# Interface_board.net
KiCad netlist of a schematic drawn in EAGLE
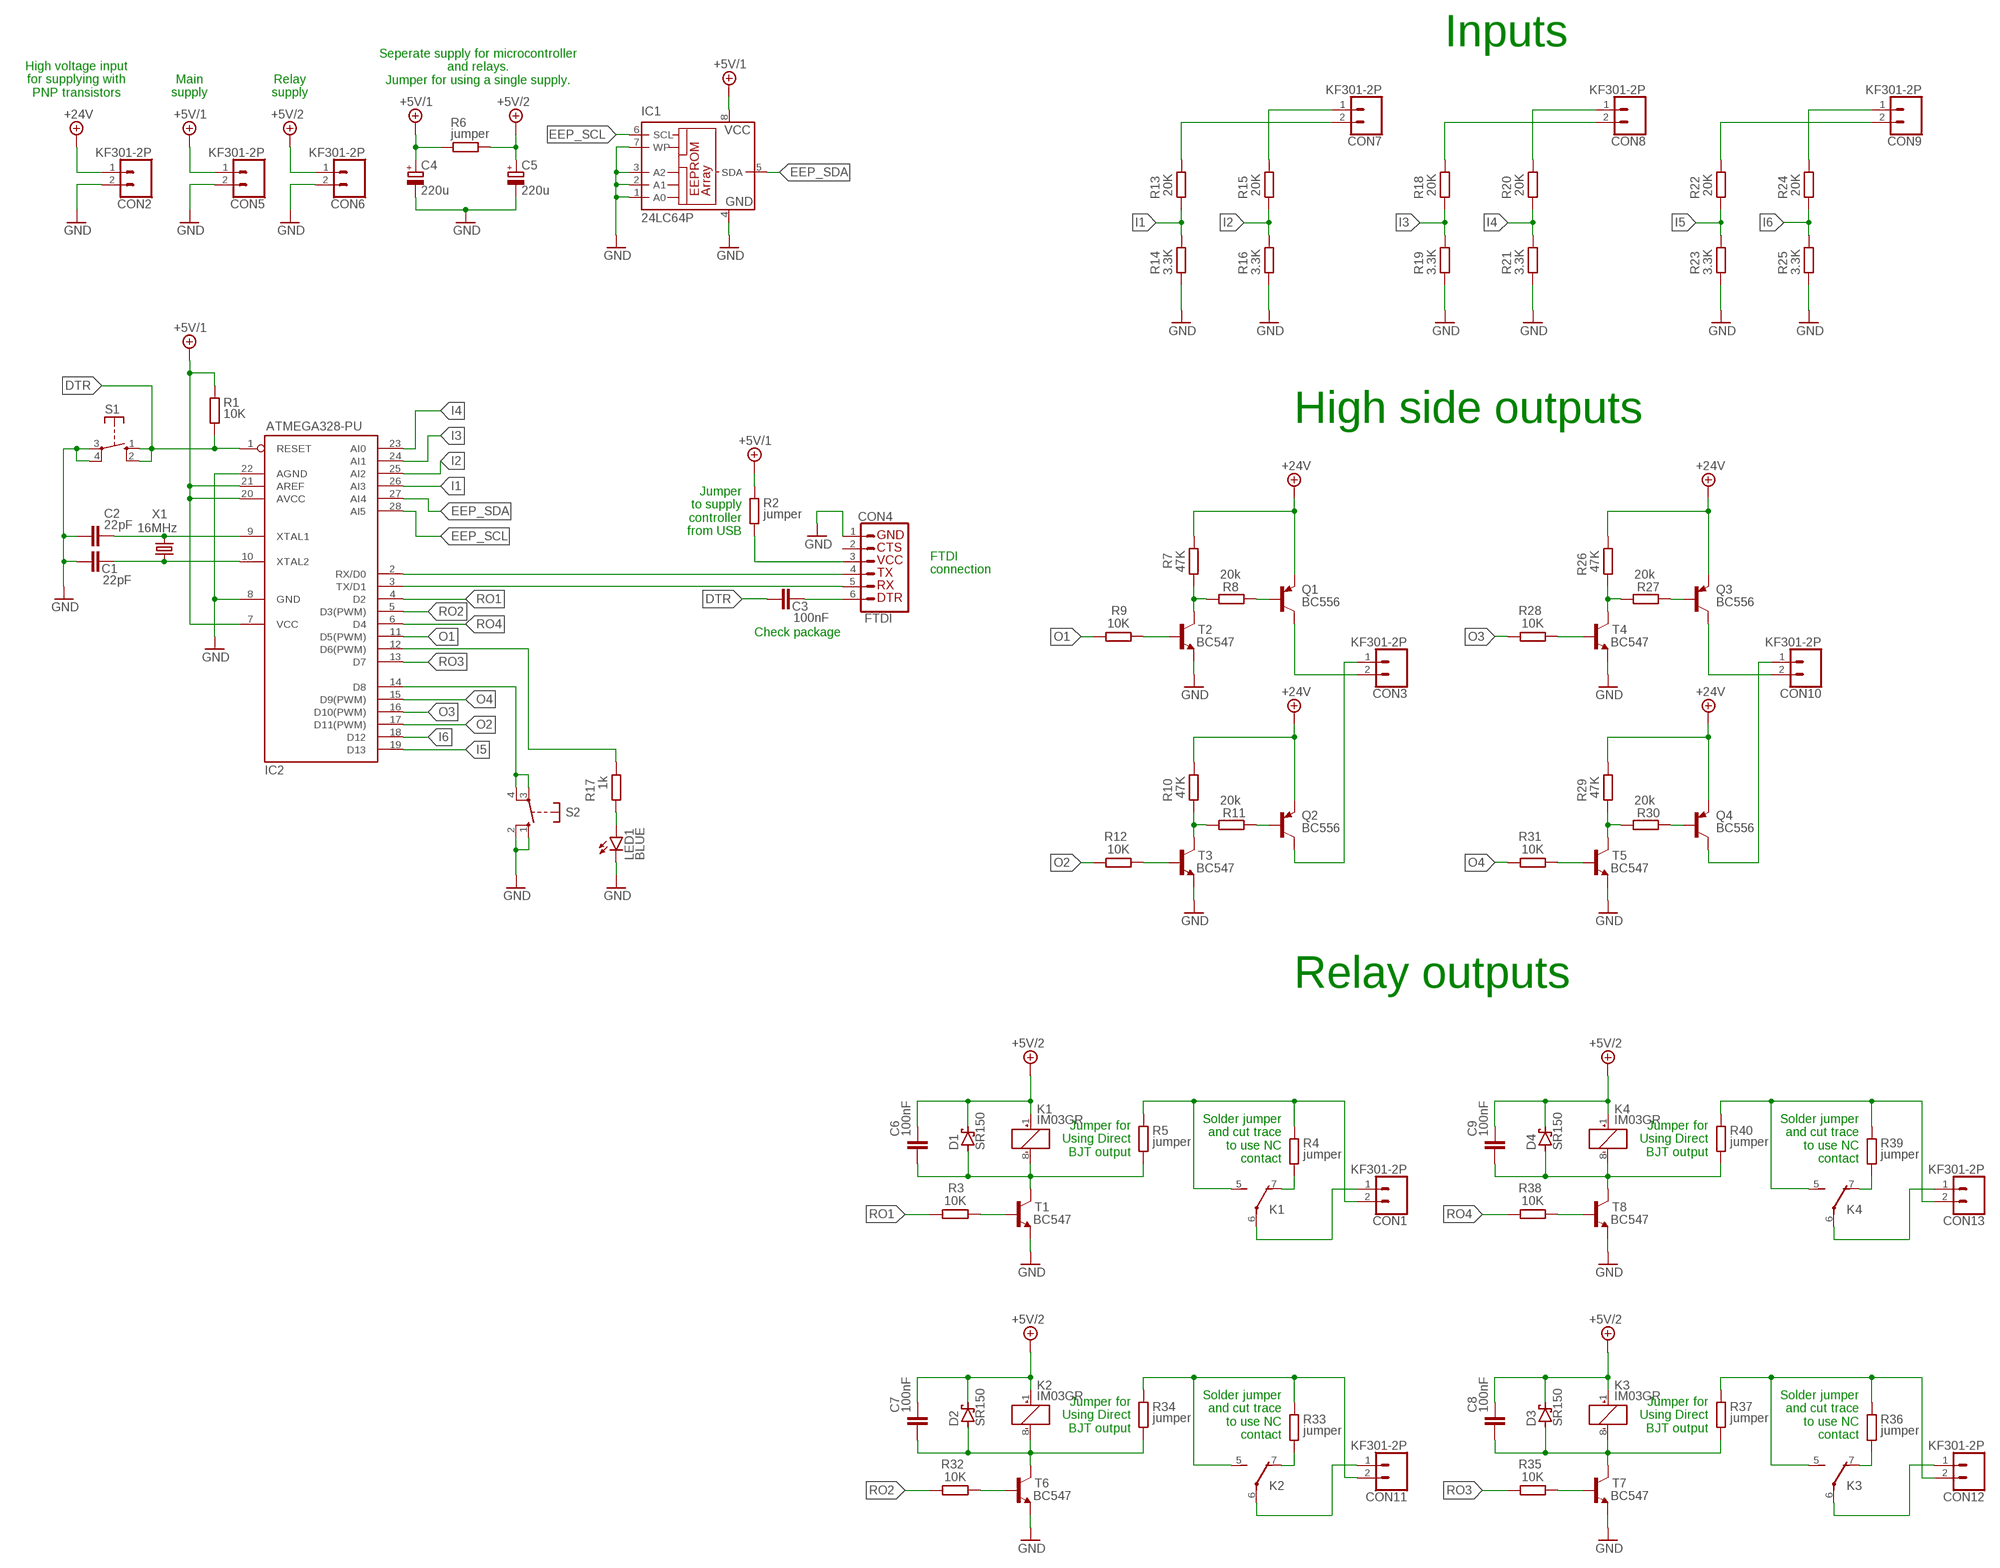
[diagram p0: schematic, sheet 1]

(export (version "E")
  (design (tool "Eeschema 10.0.6"))
  (components
    (comp (ref "C1")
      (value "22pF")
      (footprint "eagle-import:C050-024X044")
      (libsource (lib "eagle-import") (part "C-EU050-024X044"))
    )
    (comp (ref "C2")
      (value "22pF")
      (footprint "eagle-import:C050-024X044")
      (libsource (lib "eagle-import") (part "C-EU050-024X044"))
    )
    (comp (ref "C3")
      (value "100nF")
      (footprint "eagle-import:C050-024X044")
      (libsource (lib "eagle-import") (part "C-EU050-024X044"))
    )
    (comp (ref "C4")
      (value "220u")
      (footprint "eagle-import:E5-10,5")
      (libsource (lib "eagle-import") (part "CPOL-EUE5-10.5"))
    )
    (comp (ref "C5")
      (value "220u")
      (footprint "eagle-import:E5-10,5")
      (libsource (lib "eagle-import") (part "CPOL-EUE5-10.5"))
    )
    (comp (ref "C6")
      (value "100nF")
      (footprint "eagle-import:C050-024X044")
      (libsource (lib "eagle-import") (part "C-EU050-024X044"))
    )
    (comp (ref "C7")
      (value "100nF")
      (footprint "eagle-import:C050-024X044")
      (libsource (lib "eagle-import") (part "C-EU050-024X044"))
    )
    (comp (ref "C8")
      (value "100nF")
      (footprint "eagle-import:C050-024X044")
      (libsource (lib "eagle-import") (part "C-EU050-024X044"))
    )
    (comp (ref "C9")
      (value "100nF")
      (footprint "eagle-import:C050-024X044")
      (libsource (lib "eagle-import") (part "C-EU050-024X044"))
    )
    (comp (ref "CON1")
      (value "KF301-2P")
      (footprint "eagle-import:KF301-2P")
      (libsource (lib "eagle-import") (part "KF301-2P"))
    )
    (comp (ref "CON2")
      (value "KF301-2P")
      (footprint "eagle-import:KF301-2P")
      (libsource (lib "eagle-import") (part "KF301-2P"))
    )
    (comp (ref "CON3")
      (value "KF301-2P")
      (footprint "eagle-import:KF301-2P")
      (libsource (lib "eagle-import") (part "KF301-2P"))
    )
    (comp (ref "CON4")
      (value "FTDI")
      (footprint "eagle-import:1X06_W_REC_GND")
      (libsource (lib "eagle-import") (part "FTDI_CONN"))
    )
    (comp (ref "CON5")
      (value "KF301-2P")
      (footprint "eagle-import:KF301-2P")
      (libsource (lib "eagle-import") (part "KF301-2P"))
    )
    (comp (ref "CON6")
      (value "KF301-2P")
      (footprint "eagle-import:KF301-2P")
      (libsource (lib "eagle-import") (part "KF301-2P"))
    )
    (comp (ref "CON7")
      (value "KF301-2P")
      (footprint "eagle-import:KF301-2P")
      (libsource (lib "eagle-import") (part "KF301-2P"))
    )
    (comp (ref "CON8")
      (value "KF301-2P")
      (footprint "eagle-import:KF301-2P")
      (libsource (lib "eagle-import") (part "KF301-2P"))
    )
    (comp (ref "CON9")
      (value "KF301-2P")
      (footprint "eagle-import:KF301-2P")
      (libsource (lib "eagle-import") (part "KF301-2P"))
    )
    (comp (ref "CON10")
      (value "KF301-2P")
      (footprint "eagle-import:KF301-2P")
      (libsource (lib "eagle-import") (part "KF301-2P"))
    )
    (comp (ref "CON11")
      (value "KF301-2P")
      (footprint "eagle-import:KF301-2P")
      (libsource (lib "eagle-import") (part "KF301-2P"))
    )
    (comp (ref "CON12")
      (value "KF301-2P")
      (footprint "eagle-import:KF301-2P")
      (libsource (lib "eagle-import") (part "KF301-2P"))
    )
    (comp (ref "CON13")
      (value "KF301-2P")
      (footprint "eagle-import:KF301-2P")
      (libsource (lib "eagle-import") (part "KF301-2P"))
    )
    (comp (ref "D1")
      (value "SR150")
      (footprint "eagle-import:DO41-7.6")
      (libsource (lib "eagle-import") (part "1N5817-B"))
    )
    (comp (ref "D2")
      (value "SR150")
      (footprint "eagle-import:DO41-7.6")
      (libsource (lib "eagle-import") (part "1N5817-B"))
    )
    (comp (ref "D3")
      (value "SR150")
      (footprint "eagle-import:DO41-7.6")
      (libsource (lib "eagle-import") (part "1N5817-B"))
    )
    (comp (ref "D4")
      (value "SR150")
      (footprint "eagle-import:DO41-7.6")
      (libsource (lib "eagle-import") (part "1N5817-B"))
    )
    (comp (ref "IC1")
      (value "24LC64P")
      (footprint "eagle-import:DIL8")
      (fields (field (name "MF") "MICROCHIP") (field (name "MPN") "24LC64-I/P"))
      (libsource (lib "eagle-import") (part "24PLC64"))
    )
    (comp (ref "IC2")
      (value "ATMEGA328-PU")
      (footprint "eagle-import:DIL28-3")
      (libsource (lib "eagle-import") (part "328-PU_ARDUINO_F"))
    )
    (comp (ref "K1")
      (value "IM03GR")
      (footprint "eagle-import:IM03GR")
      (libsource (lib "eagle-import") (part "IM03GR"))
    )
    (comp (ref "K2")
      (value "IM03GR")
      (footprint "eagle-import:IM03GR")
      (libsource (lib "eagle-import") (part "IM03GR"))
    )
    (comp (ref "K3")
      (value "IM03GR")
      (footprint "eagle-import:IM03GR")
      (libsource (lib "eagle-import") (part "IM03GR"))
    )
    (comp (ref "K4")
      (value "IM03GR")
      (footprint "eagle-import:IM03GR")
      (libsource (lib "eagle-import") (part "IM03GR"))
    )
    (comp (ref "LED1")
      (value "BLUE")
      (footprint "eagle-import:LED5MM")
      (libsource (lib "eagle-import") (part "LED5MM"))
    )
    (comp (ref "Q1")
      (value "BC556")
      (footprint "eagle-import:TO92-EBC")
      (libsource (lib "eagle-import") (part "BC556"))
    )
    (comp (ref "Q2")
      (value "BC556")
      (footprint "eagle-import:TO92-EBC")
      (libsource (lib "eagle-import") (part "BC556"))
    )
    (comp (ref "Q3")
      (value "BC556")
      (footprint "eagle-import:TO92-EBC")
      (libsource (lib "eagle-import") (part "BC556"))
    )
    (comp (ref "Q4")
      (value "BC556")
      (footprint "eagle-import:TO92-EBC")
      (libsource (lib "eagle-import") (part "BC556"))
    )
    (comp (ref "R1")
      (value "10K")
      (footprint "eagle-import:0204_7")
      (libsource (lib "eagle-import") (part "R-EU_0204/7"))
    )
    (comp (ref "R2")
      (value "jumper")
      (footprint "eagle-import:R0805")
      (libsource (lib "eagle-import") (part "R-EU_R0805"))
    )
    (comp (ref "R3")
      (value "10K")
      (footprint "eagle-import:0204_7")
      (libsource (lib "eagle-import") (part "R-EU_0204/7"))
    )
    (comp (ref "R4")
      (value "jumper")
      (footprint "eagle-import:R0805")
      (libsource (lib "eagle-import") (part "R-EU_R0805"))
    )
    (comp (ref "R5")
      (value "jumper")
      (footprint "eagle-import:R0805")
      (libsource (lib "eagle-import") (part "R-EU_R0805"))
    )
    (comp (ref "R6")
      (value "jumper")
      (footprint "eagle-import:R0805")
      (libsource (lib "eagle-import") (part "R-EU_R0805"))
    )
    (comp (ref "R7")
      (value "47K")
      (footprint "eagle-import:0204_7")
      (libsource (lib "eagle-import") (part "R-EU_0204/7"))
    )
    (comp (ref "R8")
      (value "20k")
      (footprint "eagle-import:0204_7")
      (libsource (lib "eagle-import") (part "R-EU_0204/7"))
    )
    (comp (ref "R9")
      (value "10K")
      (footprint "eagle-import:0204_7")
      (libsource (lib "eagle-import") (part "R-EU_0204/7"))
    )
    (comp (ref "R10")
      (value "47K")
      (footprint "eagle-import:0204_7")
      (libsource (lib "eagle-import") (part "R-EU_0204/7"))
    )
    (comp (ref "R11")
      (value "20k")
      (footprint "eagle-import:0204_7")
      (libsource (lib "eagle-import") (part "R-EU_0204/7"))
    )
    (comp (ref "R12")
      (value "10K")
      (footprint "eagle-import:0204_7")
      (libsource (lib "eagle-import") (part "R-EU_0204/7"))
    )
    (comp (ref "R13")
      (value "20K")
      (footprint "eagle-import:0204_7")
      (libsource (lib "eagle-import") (part "R-EU_0204/7"))
    )
    (comp (ref "R14")
      (value "3.3K")
      (footprint "eagle-import:0204_7")
      (libsource (lib "eagle-import") (part "R-EU_0204/7"))
    )
    (comp (ref "R15")
      (value "20K")
      (footprint "eagle-import:0204_7")
      (libsource (lib "eagle-import") (part "R-EU_0204/7"))
    )
    (comp (ref "R16")
      (value "3.3K")
      (footprint "eagle-import:0204_7")
      (libsource (lib "eagle-import") (part "R-EU_0204/7"))
    )
    (comp (ref "R17")
      (value "1k")
      (footprint "eagle-import:0204_7")
      (libsource (lib "eagle-import") (part "R-EU_0204/7"))
    )
    (comp (ref "R18")
      (value "20K")
      (footprint "eagle-import:0204_7")
      (libsource (lib "eagle-import") (part "R-EU_0204/7"))
    )
    (comp (ref "R19")
      (value "3.3K")
      (footprint "eagle-import:0204_7")
      (libsource (lib "eagle-import") (part "R-EU_0204/7"))
    )
    (comp (ref "R20")
      (value "20K")
      (footprint "eagle-import:0204_7")
      (libsource (lib "eagle-import") (part "R-EU_0204/7"))
    )
    (comp (ref "R21")
      (value "3.3K")
      (footprint "eagle-import:0204_7")
      (libsource (lib "eagle-import") (part "R-EU_0204/7"))
    )
    (comp (ref "R22")
      (value "20K")
      (footprint "eagle-import:0204_7")
      (libsource (lib "eagle-import") (part "R-EU_0204/7"))
    )
    (comp (ref "R23")
      (value "3.3K")
      (footprint "eagle-import:0204_7")
      (libsource (lib "eagle-import") (part "R-EU_0204/7"))
    )
    (comp (ref "R24")
      (value "20K")
      (footprint "eagle-import:0204_7")
      (libsource (lib "eagle-import") (part "R-EU_0204/7"))
    )
    (comp (ref "R25")
      (value "3.3K")
      (footprint "eagle-import:0204_7")
      (libsource (lib "eagle-import") (part "R-EU_0204/7"))
    )
    (comp (ref "R26")
      (value "47K")
      (footprint "eagle-import:0204_7")
      (libsource (lib "eagle-import") (part "R-EU_0204/7"))
    )
    (comp (ref "R27")
      (value "20k")
      (footprint "eagle-import:0204_7")
      (libsource (lib "eagle-import") (part "R-EU_0204/7"))
    )
    (comp (ref "R28")
      (value "10K")
      (footprint "eagle-import:0204_7")
      (libsource (lib "eagle-import") (part "R-EU_0204/7"))
    )
    (comp (ref "R29")
      (value "47K")
      (footprint "eagle-import:0204_7")
      (libsource (lib "eagle-import") (part "R-EU_0204/7"))
    )
    (comp (ref "R30")
      (value "20k")
      (footprint "eagle-import:0204_7")
      (libsource (lib "eagle-import") (part "R-EU_0204/7"))
    )
    (comp (ref "R31")
      (value "10K")
      (footprint "eagle-import:0204_7")
      (libsource (lib "eagle-import") (part "R-EU_0204/7"))
    )
    (comp (ref "R32")
      (value "10K")
      (footprint "eagle-import:0204_7")
      (libsource (lib "eagle-import") (part "R-EU_0204/7"))
    )
    (comp (ref "R33")
      (value "jumper")
      (footprint "eagle-import:R0805")
      (libsource (lib "eagle-import") (part "R-EU_R0805"))
    )
    (comp (ref "R34")
      (value "jumper")
      (footprint "eagle-import:R0805")
      (libsource (lib "eagle-import") (part "R-EU_R0805"))
    )
    (comp (ref "R35")
      (value "10K")
      (footprint "eagle-import:0204_7")
      (libsource (lib "eagle-import") (part "R-EU_0204/7"))
    )
    (comp (ref "R36")
      (value "jumper")
      (footprint "eagle-import:R0805")
      (libsource (lib "eagle-import") (part "R-EU_R0805"))
    )
    (comp (ref "R37")
      (value "jumper")
      (footprint "eagle-import:R0805")
      (libsource (lib "eagle-import") (part "R-EU_R0805"))
    )
    (comp (ref "R38")
      (value "10K")
      (footprint "eagle-import:0204_7")
      (libsource (lib "eagle-import") (part "R-EU_0204/7"))
    )
    (comp (ref "R39")
      (value "jumper")
      (footprint "eagle-import:R0805")
      (libsource (lib "eagle-import") (part "R-EU_R0805"))
    )
    (comp (ref "R40")
      (value "jumper")
      (footprint "eagle-import:R0805")
      (libsource (lib "eagle-import") (part "R-EU_R0805"))
    )
    (comp (ref "S1")
      (value "RACON12")
      (footprint "eagle-import:RACON12")
      (libsource (lib "eagle-import") (part "RACON12"))
    )
    (comp (ref "S2")
      (value "RACON12")
      (footprint "eagle-import:RACON12")
      (libsource (lib "eagle-import") (part "RACON12"))
    )
    (comp (ref "T1")
      (value "BC547")
      (footprint "eagle-import:TO92")
      (libsource (lib "eagle-import") (part "BC547"))
    )
    (comp (ref "T2")
      (value "BC547")
      (footprint "eagle-import:TO92")
      (libsource (lib "eagle-import") (part "BC547"))
    )
    (comp (ref "T3")
      (value "BC547")
      (footprint "eagle-import:TO92")
      (libsource (lib "eagle-import") (part "BC547"))
    )
    (comp (ref "T4")
      (value "BC547")
      (footprint "eagle-import:TO92")
      (libsource (lib "eagle-import") (part "BC547"))
    )
    (comp (ref "T5")
      (value "BC547")
      (footprint "eagle-import:TO92")
      (libsource (lib "eagle-import") (part "BC547"))
    )
    (comp (ref "T6")
      (value "BC547")
      (footprint "eagle-import:TO92")
      (libsource (lib "eagle-import") (part "BC547"))
    )
    (comp (ref "T7")
      (value "BC547")
      (footprint "eagle-import:TO92")
      (libsource (lib "eagle-import") (part "BC547"))
    )
    (comp (ref "T8")
      (value "BC547")
      (footprint "eagle-import:TO92")
      (libsource (lib "eagle-import") (part "BC547"))
    )
    (comp (ref "X1")
      (value "16MHz")
      (footprint "eagle-import:HC49")
      (libsource (lib "eagle-import") (part "CRYSTALS-NOGND-HC49"))
    )
  )
  (nets
    (net (code "1") (name "+5V{slash}1") (class "Default")
      (node (ref "C4") (pin "+") (pinfunction "+_+") (pintype "passive"))
      (node (ref "CON5") (pin "1") (pinfunction "1_1") (pintype "passive"))
      (node (ref "IC1") (pin "8") (pinfunction "VCC_8") (pintype "power_in"))
      (node (ref "IC2") (pin "20") (pinfunction "AVCC_20") (pintype "bidirectional"))
      (node (ref "IC2") (pin "21") (pinfunction "AREF_21") (pintype "bidirectional"))
      (node (ref "IC2") (pin "7") (pinfunction "VCC_7") (pintype "bidirectional"))
      (node (ref "R1") (pin "1") (pinfunction "1_1") (pintype "passive"))
      (node (ref "R2") (pin "1") (pinfunction "1_1") (pintype "passive"))
      (node (ref "R6") (pin "1") (pinfunction "1_1") (pintype "passive"))
    )
    (net (code "2") (name "+5V{slash}2") (class "Default")
      (node (ref "C5") (pin "+") (pinfunction "+_+") (pintype "passive"))
      (node (ref "C6") (pin "1") (pinfunction "1_1") (pintype "passive"))
      (node (ref "C7") (pin "1") (pinfunction "1_1") (pintype "passive"))
      (node (ref "C8") (pin "1") (pinfunction "1_1") (pintype "passive"))
      (node (ref "C9") (pin "1") (pinfunction "1_1") (pintype "passive"))
      (node (ref "CON6") (pin "1") (pinfunction "1_1") (pintype "passive"))
      (node (ref "D1") (pin "C") (pinfunction "C_C") (pintype "passive"))
      (node (ref "D2") (pin "C") (pinfunction "C_C") (pintype "passive"))
      (node (ref "D3") (pin "C") (pinfunction "C_C") (pintype "passive"))
      (node (ref "D4") (pin "C") (pinfunction "C_C") (pintype "passive"))
      (node (ref "K1") (pin "1") (pinfunction "+_1") (pintype "passive"))
      (node (ref "K2") (pin "1") (pinfunction "+_1") (pintype "passive"))
      (node (ref "K3") (pin "1") (pinfunction "+_1") (pintype "passive"))
      (node (ref "K4") (pin "1") (pinfunction "+_1") (pintype "passive"))
      (node (ref "R6") (pin "2") (pinfunction "2_2") (pintype "passive"))
    )
    (net (code "3") (name "+24V") (class "Default")
      (node (ref "CON2") (pin "1") (pinfunction "1_1") (pintype "passive"))
      (node (ref "Q1") (pin "E") (pinfunction "E_E") (pintype "passive"))
      (node (ref "Q2") (pin "E") (pinfunction "E_E") (pintype "passive"))
      (node (ref "Q3") (pin "E") (pinfunction "E_E") (pintype "passive"))
      (node (ref "Q4") (pin "E") (pinfunction "E_E") (pintype "passive"))
      (node (ref "R10") (pin "2") (pinfunction "2_2") (pintype "passive"))
      (node (ref "R26") (pin "2") (pinfunction "2_2") (pintype "passive"))
      (node (ref "R29") (pin "2") (pinfunction "2_2") (pintype "passive"))
      (node (ref "R7") (pin "2") (pinfunction "2_2") (pintype "passive"))
    )
    (net (code "4") (name "DTR") (class "Default")
      (node (ref "C3") (pin "2") (pinfunction "2_2") (pintype "passive"))
      (node (ref "IC2") (pin "1") (pinfunction "RESET_1") (pintype "bidirectional"))
      (node (ref "R1") (pin "2") (pinfunction "2_2") (pintype "passive"))
      (node (ref "S1") (pin "1") (pinfunction "S_1") (pintype "passive"))
      (node (ref "S1") (pin "2") (pinfunction "S_2") (pintype "passive"))
    )
    (net (code "5") (name "EEP_SCL") (class "Default")
      (node (ref "IC1") (pin "6") (pinfunction "SCL_6") (pintype "input"))
      (node (ref "IC2") (pin "28") (pinfunction "AI5_28") (pintype "bidirectional"))
    )
    (net (code "6") (name "EEP_SDA") (class "Default")
      (node (ref "IC1") (pin "5") (pinfunction "SDA_5") (pintype "bidirectional"))
      (node (ref "IC2") (pin "27") (pinfunction "AI4_27") (pintype "bidirectional"))
    )
    (net (code "7") (name "GND") (class "Default")
      (node (ref "C1") (pin "2") (pinfunction "2_2") (pintype "passive"))
      (node (ref "C2") (pin "2") (pinfunction "2_2") (pintype "passive"))
      (node (ref "C4") (pin "-") (pinfunction "-_-") (pintype "passive"))
      (node (ref "C5") (pin "-") (pinfunction "-_-") (pintype "passive"))
      (node (ref "CON2") (pin "2") (pinfunction "2_2") (pintype "passive"))
      (node (ref "CON4") (pin "1") (pinfunction "6_1") (pintype "passive"))
      (node (ref "CON5") (pin "2") (pinfunction "2_2") (pintype "passive"))
      (node (ref "CON6") (pin "2") (pinfunction "2_2") (pintype "passive"))
      (node (ref "IC1") (pin "1") (pinfunction "A0_1") (pintype "input"))
      (node (ref "IC1") (pin "2") (pinfunction "A1_2") (pintype "input"))
      (node (ref "IC1") (pin "3") (pinfunction "A2_3") (pintype "input"))
      (node (ref "IC1") (pin "4") (pinfunction "GND_4") (pintype "power_in"))
      (node (ref "IC1") (pin "7") (pinfunction "WP_7") (pintype "input"))
      (node (ref "IC2") (pin "22") (pinfunction "AGND_22") (pintype "bidirectional"))
      (node (ref "IC2") (pin "8") (pinfunction "GND_8") (pintype "bidirectional"))
      (node (ref "LED1") (pin "K") (pinfunction "C_K") (pintype "passive"))
      (node (ref "R14") (pin "1") (pinfunction "1_1") (pintype "passive"))
      (node (ref "R16") (pin "1") (pinfunction "1_1") (pintype "passive"))
      (node (ref "R19") (pin "1") (pinfunction "1_1") (pintype "passive"))
      (node (ref "R21") (pin "1") (pinfunction "1_1") (pintype "passive"))
      (node (ref "R23") (pin "1") (pinfunction "1_1") (pintype "passive"))
      (node (ref "R25") (pin "1") (pinfunction "1_1") (pintype "passive"))
      (node (ref "S1") (pin "3") (pinfunction "P_3") (pintype "passive"))
      (node (ref "S1") (pin "4") (pinfunction "P_4") (pintype "passive"))
      (node (ref "S2") (pin "1") (pinfunction "S_1") (pintype "passive"))
      (node (ref "S2") (pin "2") (pinfunction "S_2") (pintype "passive"))
      (node (ref "T1") (pin "1") (pinfunction "E_1") (pintype "passive"))
      (node (ref "T2") (pin "1") (pinfunction "E_1") (pintype "passive"))
      (node (ref "T3") (pin "1") (pinfunction "E_1") (pintype "passive"))
      (node (ref "T4") (pin "1") (pinfunction "E_1") (pintype "passive"))
      (node (ref "T5") (pin "1") (pinfunction "E_1") (pintype "passive"))
      (node (ref "T6") (pin "1") (pinfunction "E_1") (pintype "passive"))
      (node (ref "T7") (pin "1") (pinfunction "E_1") (pintype "passive"))
      (node (ref "T8") (pin "1") (pinfunction "E_1") (pintype "passive"))
    )
    (net (code "8") (name "I1") (class "Default")
      (node (ref "IC2") (pin "26") (pinfunction "AI3_26") (pintype "bidirectional"))
      (node (ref "R13") (pin "1") (pinfunction "1_1") (pintype "passive"))
      (node (ref "R14") (pin "2") (pinfunction "2_2") (pintype "passive"))
    )
    (net (code "9") (name "I2") (class "Default")
      (node (ref "IC2") (pin "25") (pinfunction "AI2_25") (pintype "bidirectional"))
      (node (ref "R15") (pin "1") (pinfunction "1_1") (pintype "passive"))
      (node (ref "R16") (pin "2") (pinfunction "2_2") (pintype "passive"))
    )
    (net (code "10") (name "I3") (class "Default")
      (node (ref "IC2") (pin "24") (pinfunction "AI1_24") (pintype "bidirectional"))
      (node (ref "R18") (pin "1") (pinfunction "1_1") (pintype "passive"))
      (node (ref "R19") (pin "2") (pinfunction "2_2") (pintype "passive"))
    )
    (net (code "11") (name "I4") (class "Default")
      (node (ref "IC2") (pin "23") (pinfunction "AI0_23") (pintype "bidirectional"))
      (node (ref "R20") (pin "1") (pinfunction "1_1") (pintype "passive"))
      (node (ref "R21") (pin "2") (pinfunction "2_2") (pintype "passive"))
    )
    (net (code "12") (name "I5") (class "Default")
      (node (ref "IC2") (pin "19") (pinfunction "D13_19") (pintype "bidirectional"))
      (node (ref "R22") (pin "1") (pinfunction "1_1") (pintype "passive"))
      (node (ref "R23") (pin "2") (pinfunction "2_2") (pintype "passive"))
    )
    (net (code "13") (name "I6") (class "Default")
      (node (ref "IC2") (pin "18") (pinfunction "D12_18") (pintype "bidirectional"))
      (node (ref "R24") (pin "1") (pinfunction "1_1") (pintype "passive"))
      (node (ref "R25") (pin "2") (pinfunction "2_2") (pintype "passive"))
    )
    (net (code "14") (name "Net-(CON3-Pad1)") (class "Default")
      (node (ref "CON3") (pin "1") (pinfunction "1_1") (pintype "passive"))
      (node (ref "Q2") (pin "C") (pinfunction "C_C") (pintype "passive"))
    )
    (net (code "15") (name "Net-(CON3-Pad2)") (class "Default")
      (node (ref "CON3") (pin "2") (pinfunction "2_2") (pintype "passive"))
      (node (ref "Q1") (pin "C") (pinfunction "C_C") (pintype "passive"))
    )
    (net (code "16") (name "Net-(CON4-1)") (class "Default")
      (node (ref "C3") (pin "1") (pinfunction "1_1") (pintype "passive"))
      (node (ref "CON4") (pin "6") (pinfunction "1_6") (pintype "passive"))
    )
    (net (code "17") (name "Net-(CON4-2)") (class "Default")
      (node (ref "CON4") (pin "5") (pinfunction "2_5") (pintype "passive"))
      (node (ref "IC2") (pin "3") (pinfunction "TX/D1_3") (pintype "bidirectional"))
    )
    (net (code "18") (name "Net-(CON4-3)") (class "Default")
      (node (ref "CON4") (pin "4") (pinfunction "3_4") (pintype "passive"))
      (node (ref "IC2") (pin "2") (pinfunction "RX/D0_2") (pintype "bidirectional"))
    )
    (net (code "19") (name "Net-(CON4-4)") (class "Default")
      (node (ref "CON4") (pin "3") (pinfunction "4_3") (pintype "passive"))
      (node (ref "R2") (pin "2") (pinfunction "2_2") (pintype "passive"))
    )
    (net (code "20") (name "Net-(CON7-Pad1)") (class "Default")
      (node (ref "CON7") (pin "1") (pinfunction "1_1") (pintype "passive"))
      (node (ref "R15") (pin "2") (pinfunction "2_2") (pintype "passive"))
    )
    (net (code "21") (name "Net-(CON7-Pad2)") (class "Default")
      (node (ref "CON7") (pin "2") (pinfunction "2_2") (pintype "passive"))
      (node (ref "R13") (pin "2") (pinfunction "2_2") (pintype "passive"))
    )
    (net (code "22") (name "Net-(CON8-Pad1)") (class "Default")
      (node (ref "CON8") (pin "1") (pinfunction "1_1") (pintype "passive"))
      (node (ref "R20") (pin "2") (pinfunction "2_2") (pintype "passive"))
    )
    (net (code "23") (name "Net-(CON8-Pad2)") (class "Default")
      (node (ref "CON8") (pin "2") (pinfunction "2_2") (pintype "passive"))
      (node (ref "R18") (pin "2") (pinfunction "2_2") (pintype "passive"))
    )
    (net (code "24") (name "Net-(CON9-Pad1)") (class "Default")
      (node (ref "CON9") (pin "1") (pinfunction "1_1") (pintype "passive"))
      (node (ref "R24") (pin "2") (pinfunction "2_2") (pintype "passive"))
    )
    (net (code "25") (name "Net-(CON9-Pad2)") (class "Default")
      (node (ref "CON9") (pin "2") (pinfunction "2_2") (pintype "passive"))
      (node (ref "R22") (pin "2") (pinfunction "2_2") (pintype "passive"))
    )
    (net (code "26") (name "Net-(CON10-Pad1)") (class "Default")
      (node (ref "CON10") (pin "1") (pinfunction "1_1") (pintype "passive"))
      (node (ref "Q4") (pin "C") (pinfunction "C_C") (pintype "passive"))
    )
    (net (code "27") (name "Net-(CON10-Pad2)") (class "Default")
      (node (ref "CON10") (pin "2") (pinfunction "2_2") (pintype "passive"))
      (node (ref "Q3") (pin "C") (pinfunction "C_C") (pintype "passive"))
    )
    (net (code "28") (name "Net-(IC2-D6(PWM))") (class "Default")
      (node (ref "IC2") (pin "12") (pinfunction "D6(PWM)_12") (pintype "bidirectional"))
      (node (ref "R17") (pin "2") (pinfunction "2_2") (pintype "passive"))
    )
    (net (code "29") (name "Net-(IC2-D8)") (class "Default")
      (node (ref "IC2") (pin "14") (pinfunction "D8_14") (pintype "bidirectional"))
      (node (ref "S2") (pin "3") (pinfunction "P_3") (pintype "passive"))
      (node (ref "S2") (pin "4") (pinfunction "P_4") (pintype "passive"))
    )
    (net (code "30") (name "Net-(IC2-XTAL1)") (class "Default")
      (node (ref "C2") (pin "1") (pinfunction "1_1") (pintype "passive"))
      (node (ref "IC2") (pin "9") (pinfunction "XTAL1_9") (pintype "bidirectional"))
      (node (ref "X1") (pin "1") (pinfunction "1_1") (pintype "passive"))
    )
    (net (code "31") (name "Net-(IC2-XTAL2)") (class "Default")
      (node (ref "C1") (pin "1") (pinfunction "1_1") (pintype "passive"))
      (node (ref "IC2") (pin "10") (pinfunction "XTAL2_10") (pintype "bidirectional"))
      (node (ref "X1") (pin "2") (pinfunction "2_2") (pintype "passive"))
    )
    (net (code "32") (name "Net-(K1B-O)") (class "Default")
      (node (ref "K1") (pin "7") (pinfunction "O_7") (pintype "passive"))
      (node (ref "R4") (pin "2") (pinfunction "2_2") (pintype "passive"))
    )
    (net (code "33") (name "Net-(K1B-P)") (class "Default")
      (node (ref "CON1") (pin "1") (pinfunction "1_1") (pintype "passive"))
      (node (ref "K1") (pin "6") (pinfunction "P_6") (pintype "passive"))
    )
    (net (code "34") (name "Net-(K1B-S)") (class "Default")
      (node (ref "CON1") (pin "2") (pinfunction "2_2") (pintype "passive"))
      (node (ref "K1") (pin "5") (pinfunction "S_5") (pintype "passive"))
      (node (ref "R4") (pin "1") (pinfunction "1_1") (pintype "passive"))
      (node (ref "R5") (pin "1") (pinfunction "1_1") (pintype "passive"))
    )
    (net (code "35") (name "Net-(K1C--)") (class "Default")
      (node (ref "C6") (pin "2") (pinfunction "2_2") (pintype "passive"))
      (node (ref "D1") (pin "A") (pinfunction "A_A") (pintype "passive"))
      (node (ref "K1") (pin "8") (pinfunction "-_8") (pintype "passive"))
      (node (ref "R5") (pin "2") (pinfunction "2_2") (pintype "passive"))
      (node (ref "T1") (pin "3") (pinfunction "C_3") (pintype "passive"))
    )
    (net (code "36") (name "Net-(K2B-O)") (class "Default")
      (node (ref "K2") (pin "7") (pinfunction "O_7") (pintype "passive"))
      (node (ref "R33") (pin "2") (pinfunction "2_2") (pintype "passive"))
    )
    (net (code "37") (name "Net-(K2B-P)") (class "Default")
      (node (ref "CON11") (pin "1") (pinfunction "1_1") (pintype "passive"))
      (node (ref "K2") (pin "6") (pinfunction "P_6") (pintype "passive"))
    )
    (net (code "38") (name "Net-(K2B-S)") (class "Default")
      (node (ref "CON11") (pin "2") (pinfunction "2_2") (pintype "passive"))
      (node (ref "K2") (pin "5") (pinfunction "S_5") (pintype "passive"))
      (node (ref "R33") (pin "1") (pinfunction "1_1") (pintype "passive"))
      (node (ref "R34") (pin "1") (pinfunction "1_1") (pintype "passive"))
    )
    (net (code "39") (name "Net-(K2C--)") (class "Default")
      (node (ref "C7") (pin "2") (pinfunction "2_2") (pintype "passive"))
      (node (ref "D2") (pin "A") (pinfunction "A_A") (pintype "passive"))
      (node (ref "K2") (pin "8") (pinfunction "-_8") (pintype "passive"))
      (node (ref "R34") (pin "2") (pinfunction "2_2") (pintype "passive"))
      (node (ref "T6") (pin "3") (pinfunction "C_3") (pintype "passive"))
    )
    (net (code "40") (name "Net-(K3B-O)") (class "Default")
      (node (ref "K3") (pin "7") (pinfunction "O_7") (pintype "passive"))
      (node (ref "R36") (pin "2") (pinfunction "2_2") (pintype "passive"))
    )
    (net (code "41") (name "Net-(K3B-P)") (class "Default")
      (node (ref "CON12") (pin "1") (pinfunction "1_1") (pintype "passive"))
      (node (ref "K3") (pin "6") (pinfunction "P_6") (pintype "passive"))
    )
    (net (code "42") (name "Net-(K3B-S)") (class "Default")
      (node (ref "CON12") (pin "2") (pinfunction "2_2") (pintype "passive"))
      (node (ref "K3") (pin "5") (pinfunction "S_5") (pintype "passive"))
      (node (ref "R36") (pin "1") (pinfunction "1_1") (pintype "passive"))
      (node (ref "R37") (pin "1") (pinfunction "1_1") (pintype "passive"))
    )
    (net (code "43") (name "Net-(K3C--)") (class "Default")
      (node (ref "C8") (pin "2") (pinfunction "2_2") (pintype "passive"))
      (node (ref "D3") (pin "A") (pinfunction "A_A") (pintype "passive"))
      (node (ref "K3") (pin "8") (pinfunction "-_8") (pintype "passive"))
      (node (ref "R37") (pin "2") (pinfunction "2_2") (pintype "passive"))
      (node (ref "T7") (pin "3") (pinfunction "C_3") (pintype "passive"))
    )
    (net (code "44") (name "Net-(K4B-O)") (class "Default")
      (node (ref "K4") (pin "7") (pinfunction "O_7") (pintype "passive"))
      (node (ref "R39") (pin "2") (pinfunction "2_2") (pintype "passive"))
    )
    (net (code "45") (name "Net-(K4B-P)") (class "Default")
      (node (ref "CON13") (pin "1") (pinfunction "1_1") (pintype "passive"))
      (node (ref "K4") (pin "6") (pinfunction "P_6") (pintype "passive"))
    )
    (net (code "46") (name "Net-(K4B-S)") (class "Default")
      (node (ref "CON13") (pin "2") (pinfunction "2_2") (pintype "passive"))
      (node (ref "K4") (pin "5") (pinfunction "S_5") (pintype "passive"))
      (node (ref "R39") (pin "1") (pinfunction "1_1") (pintype "passive"))
      (node (ref "R40") (pin "1") (pinfunction "1_1") (pintype "passive"))
    )
    (net (code "47") (name "Net-(K4C--)") (class "Default")
      (node (ref "C9") (pin "2") (pinfunction "2_2") (pintype "passive"))
      (node (ref "D4") (pin "A") (pinfunction "A_A") (pintype "passive"))
      (node (ref "K4") (pin "8") (pinfunction "-_8") (pintype "passive"))
      (node (ref "R40") (pin "2") (pinfunction "2_2") (pintype "passive"))
      (node (ref "T8") (pin "3") (pinfunction "C_3") (pintype "passive"))
    )
    (net (code "48") (name "Net-(LED1-PadA)") (class "Default")
      (node (ref "LED1") (pin "A") (pinfunction "A_A") (pintype "passive"))
      (node (ref "R17") (pin "1") (pinfunction "1_1") (pintype "passive"))
    )
    (net (code "49") (name "Net-(Q1-PadB)") (class "Default")
      (node (ref "Q1") (pin "B") (pinfunction "B_B") (pintype "passive"))
      (node (ref "R8") (pin "1") (pinfunction "1_1") (pintype "passive"))
    )
    (net (code "50") (name "Net-(Q2-PadB)") (class "Default")
      (node (ref "Q2") (pin "B") (pinfunction "B_B") (pintype "passive"))
      (node (ref "R11") (pin "1") (pinfunction "1_1") (pintype "passive"))
    )
    (net (code "51") (name "Net-(Q3-PadB)") (class "Default")
      (node (ref "Q3") (pin "B") (pinfunction "B_B") (pintype "passive"))
      (node (ref "R27") (pin "1") (pinfunction "1_1") (pintype "passive"))
    )
    (net (code "52") (name "Net-(Q4-PadB)") (class "Default")
      (node (ref "Q4") (pin "B") (pinfunction "B_B") (pintype "passive"))
      (node (ref "R30") (pin "1") (pinfunction "1_1") (pintype "passive"))
    )
    (net (code "53") (name "Net-(T1-B)") (class "Default")
      (node (ref "R3") (pin "2") (pinfunction "2_2") (pintype "passive"))
      (node (ref "T1") (pin "2") (pinfunction "B_2") (pintype "passive"))
    )
    (net (code "54") (name "Net-(T2-B)") (class "Default")
      (node (ref "R9") (pin "2") (pinfunction "2_2") (pintype "passive"))
      (node (ref "T2") (pin "2") (pinfunction "B_2") (pintype "passive"))
    )
    (net (code "55") (name "Net-(T2-C)") (class "Default")
      (node (ref "R7") (pin "1") (pinfunction "1_1") (pintype "passive"))
      (node (ref "R8") (pin "2") (pinfunction "2_2") (pintype "passive"))
      (node (ref "T2") (pin "3") (pinfunction "C_3") (pintype "passive"))
    )
    (net (code "56") (name "Net-(T3-B)") (class "Default")
      (node (ref "R12") (pin "2") (pinfunction "2_2") (pintype "passive"))
      (node (ref "T3") (pin "2") (pinfunction "B_2") (pintype "passive"))
    )
    (net (code "57") (name "Net-(T3-C)") (class "Default")
      (node (ref "R10") (pin "1") (pinfunction "1_1") (pintype "passive"))
      (node (ref "R11") (pin "2") (pinfunction "2_2") (pintype "passive"))
      (node (ref "T3") (pin "3") (pinfunction "C_3") (pintype "passive"))
    )
    (net (code "58") (name "Net-(T4-B)") (class "Default")
      (node (ref "R28") (pin "2") (pinfunction "2_2") (pintype "passive"))
      (node (ref "T4") (pin "2") (pinfunction "B_2") (pintype "passive"))
    )
    (net (code "59") (name "Net-(T4-C)") (class "Default")
      (node (ref "R26") (pin "1") (pinfunction "1_1") (pintype "passive"))
      (node (ref "R27") (pin "2") (pinfunction "2_2") (pintype "passive"))
      (node (ref "T4") (pin "3") (pinfunction "C_3") (pintype "passive"))
    )
    (net (code "60") (name "Net-(T5-B)") (class "Default")
      (node (ref "R31") (pin "2") (pinfunction "2_2") (pintype "passive"))
      (node (ref "T5") (pin "2") (pinfunction "B_2") (pintype "passive"))
    )
    (net (code "61") (name "Net-(T5-C)") (class "Default")
      (node (ref "R29") (pin "1") (pinfunction "1_1") (pintype "passive"))
      (node (ref "R30") (pin "2") (pinfunction "2_2") (pintype "passive"))
      (node (ref "T5") (pin "3") (pinfunction "C_3") (pintype "passive"))
    )
    (net (code "62") (name "Net-(T6-B)") (class "Default")
      (node (ref "R32") (pin "2") (pinfunction "2_2") (pintype "passive"))
      (node (ref "T6") (pin "2") (pinfunction "B_2") (pintype "passive"))
    )
    (net (code "63") (name "Net-(T7-B)") (class "Default")
      (node (ref "R35") (pin "2") (pinfunction "2_2") (pintype "passive"))
      (node (ref "T7") (pin "2") (pinfunction "B_2") (pintype "passive"))
    )
    (net (code "64") (name "Net-(T8-B)") (class "Default")
      (node (ref "R38") (pin "2") (pinfunction "2_2") (pintype "passive"))
      (node (ref "T8") (pin "2") (pinfunction "B_2") (pintype "passive"))
    )
    (net (code "65") (name "O1") (class "Default")
      (node (ref "IC2") (pin "11") (pinfunction "D5(PWM)_11") (pintype "bidirectional"))
      (node (ref "R9") (pin "1") (pinfunction "1_1") (pintype "passive"))
    )
    (net (code "66") (name "O2") (class "Default")
      (node (ref "IC2") (pin "17") (pinfunction "D11(PWM)_17") (pintype "bidirectional"))
      (node (ref "R12") (pin "1") (pinfunction "1_1") (pintype "passive"))
    )
    (net (code "67") (name "O3") (class "Default")
      (node (ref "IC2") (pin "16") (pinfunction "D10(PWM)_16") (pintype "bidirectional"))
      (node (ref "R28") (pin "1") (pinfunction "1_1") (pintype "passive"))
    )
    (net (code "68") (name "O4") (class "Default")
      (node (ref "IC2") (pin "15") (pinfunction "D9(PWM)_15") (pintype "bidirectional"))
      (node (ref "R31") (pin "1") (pinfunction "1_1") (pintype "passive"))
    )
    (net (code "69") (name "RO1") (class "Default")
      (node (ref "IC2") (pin "4") (pinfunction "D2_4") (pintype "bidirectional"))
      (node (ref "R3") (pin "1") (pinfunction "1_1") (pintype "passive"))
    )
    (net (code "70") (name "RO2") (class "Default")
      (node (ref "IC2") (pin "5") (pinfunction "D3(PWM)_5") (pintype "bidirectional"))
      (node (ref "R32") (pin "1") (pinfunction "1_1") (pintype "passive"))
    )
    (net (code "71") (name "RO3") (class "Default")
      (node (ref "IC2") (pin "13") (pinfunction "D7_13") (pintype "bidirectional"))
      (node (ref "R35") (pin "1") (pinfunction "1_1") (pintype "passive"))
    )
    (net (code "72") (name "RO4") (class "Default")
      (node (ref "IC2") (pin "6") (pinfunction "D4_6") (pintype "bidirectional"))
      (node (ref "R38") (pin "1") (pinfunction "1_1") (pintype "passive"))
    )
    (net (code "73") (name "unconnected-(CON4-5-Pad2)") (class "Default")
      (node (ref "CON4") (pin "2") (pinfunction "5_2") (pintype "passive"))
    )
  )
)
